# TCRT1.net
KiCad netlist of a schematic drawn in EAGLE
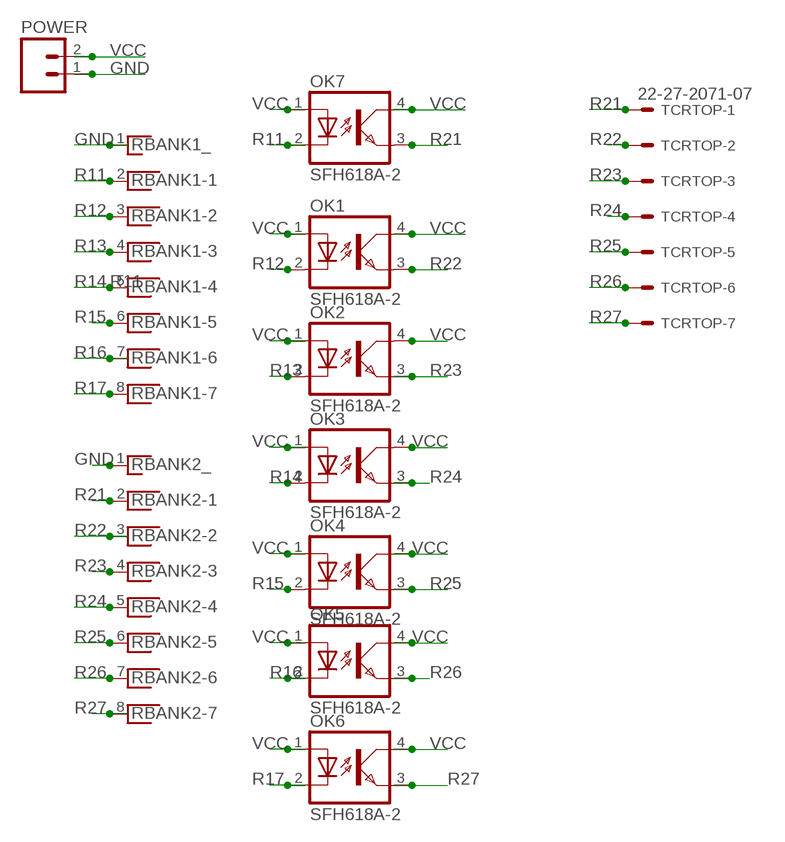
[diagram p0: schematic, sheet 1]

(export (version "E")
  (design (tool "Eeschema 10.0.6"))
  (components
    (comp (ref "OK1")
      (value "SFH618A-2")
      (footprint "eagle-import:DIP4")
      (fields (field (name "MF") "VISHAY/TELEFUNKEN"))
      (libsource (lib "eagle-import") (part "SFH618?A-2"))
    )
    (comp (ref "OK2")
      (value "SFH618A-2")
      (footprint "eagle-import:DIP4")
      (fields (field (name "MF") "VISHAY/TELEFUNKEN"))
      (libsource (lib "eagle-import") (part "SFH618?A-2"))
    )
    (comp (ref "OK3")
      (value "SFH618A-2")
      (footprint "eagle-import:DIP4")
      (fields (field (name "MF") "VISHAY/TELEFUNKEN"))
      (libsource (lib "eagle-import") (part "SFH618?A-2"))
    )
    (comp (ref "OK4")
      (value "SFH618A-2")
      (footprint "eagle-import:DIP4")
      (fields (field (name "MF") "VISHAY/TELEFUNKEN"))
      (libsource (lib "eagle-import") (part "SFH618?A-2"))
    )
    (comp (ref "OK5")
      (value "SFH618A-2")
      (footprint "eagle-import:DIP4")
      (fields (field (name "MF") "VISHAY/TELEFUNKEN"))
      (libsource (lib "eagle-import") (part "SFH618?A-2"))
    )
    (comp (ref "OK6")
      (value "SFH618A-2")
      (footprint "eagle-import:DIP4")
      (fields (field (name "MF") "VISHAY/TELEFUNKEN"))
      (libsource (lib "eagle-import") (part "SFH618?A-2"))
    )
    (comp (ref "OK7")
      (value "SFH618A-2")
      (footprint "eagle-import:DIP4")
      (fields (field (name "MF") "VISHAY/TELEFUNKEN"))
      (libsource (lib "eagle-import") (part "SFH618?A-2"))
    )
    (comp (ref "POWER")
      (value "M025MM")
      (footprint "eagle-import:SCREWTERMINAL-5MM-2")
      (libsource (lib "eagle-import") (part "M025MM"))
    )
    (comp (ref "RBANK1")
      (value "RNX7")
      (footprint "eagle-import:RN-8")
      (libsource (lib "eagle-import") (part "RNX7"))
    )
    (comp (ref "RBANK2")
      (value "RNX7")
      (footprint "eagle-import:RN-8")
      (libsource (lib "eagle-import") (part "RNX7"))
    )
    (comp (ref "TCRTOP")
      (value "22-27-2071-07")
      (footprint "eagle-import:6410-07")
      (libsource (lib "eagle-import") (part "22-?-0727-2071"))
    )
  )
  (nets
    (net (code "1") (name "/GND") (class "Default")
      (node (ref "POWER") (pin "1") (pinfunction "1_1") (pintype "passive"))
      (node (ref "RBANK1") (pin "1") (pinfunction "1_1") (pintype "passive"))
      (node (ref "RBANK2") (pin "1") (pinfunction "1_1") (pintype "passive"))
    )
    (net (code "2") (name "/R11") (class "Default")
      (node (ref "OK7") (pin "2") (pinfunction "C_2") (pintype "passive"))
      (node (ref "RBANK1") (pin "2") (pinfunction "1_2") (pintype "passive"))
    )
    (net (code "3") (name "/R12") (class "Default")
      (node (ref "OK1") (pin "2") (pinfunction "C_2") (pintype "passive"))
      (node (ref "RBANK1") (pin "3") (pinfunction "1_3") (pintype "passive"))
    )
    (net (code "4") (name "/R13") (class "Default")
      (node (ref "OK2") (pin "2") (pinfunction "C_2") (pintype "passive"))
      (node (ref "RBANK1") (pin "4") (pinfunction "1_4") (pintype "passive"))
    )
    (net (code "5") (name "/R14") (class "Default")
      (node (ref "OK3") (pin "2") (pinfunction "C_2") (pintype "passive"))
      (node (ref "RBANK1") (pin "5") (pinfunction "1_5") (pintype "passive"))
    )
    (net (code "6") (name "/R15") (class "Default")
      (node (ref "OK4") (pin "2") (pinfunction "C_2") (pintype "passive"))
      (node (ref "RBANK1") (pin "6") (pinfunction "1_6") (pintype "passive"))
    )
    (net (code "7") (name "/R16") (class "Default")
      (node (ref "OK5") (pin "2") (pinfunction "C_2") (pintype "passive"))
      (node (ref "RBANK1") (pin "7") (pinfunction "1_7") (pintype "passive"))
    )
    (net (code "8") (name "/R17") (class "Default")
      (node (ref "OK6") (pin "2") (pinfunction "C_2") (pintype "passive"))
      (node (ref "RBANK1") (pin "8") (pinfunction "1_8") (pintype "passive"))
    )
    (net (code "9") (name "/R21") (class "Default")
      (node (ref "OK7") (pin "3") (pinfunction "EMIT_3") (pintype "passive"))
      (node (ref "RBANK2") (pin "2") (pinfunction "1_2") (pintype "passive"))
      (node (ref "TCRTOP") (pin "1") (pinfunction "S_1") (pintype "passive"))
    )
    (net (code "10") (name "/R22") (class "Default")
      (node (ref "OK1") (pin "3") (pinfunction "EMIT_3") (pintype "passive"))
      (node (ref "RBANK2") (pin "3") (pinfunction "1_3") (pintype "passive"))
      (node (ref "TCRTOP") (pin "2") (pinfunction "S_2") (pintype "passive"))
    )
    (net (code "11") (name "/R23") (class "Default")
      (node (ref "OK2") (pin "3") (pinfunction "EMIT_3") (pintype "passive"))
      (node (ref "RBANK2") (pin "4") (pinfunction "1_4") (pintype "passive"))
      (node (ref "TCRTOP") (pin "3") (pinfunction "S_3") (pintype "passive"))
    )
    (net (code "12") (name "/R24") (class "Default")
      (node (ref "OK3") (pin "3") (pinfunction "EMIT_3") (pintype "passive"))
      (node (ref "RBANK2") (pin "5") (pinfunction "1_5") (pintype "passive"))
      (node (ref "TCRTOP") (pin "4") (pinfunction "S_4") (pintype "passive"))
    )
    (net (code "13") (name "/R25") (class "Default")
      (node (ref "OK4") (pin "3") (pinfunction "EMIT_3") (pintype "passive"))
      (node (ref "RBANK2") (pin "6") (pinfunction "1_6") (pintype "passive"))
      (node (ref "TCRTOP") (pin "5") (pinfunction "S_5") (pintype "passive"))
    )
    (net (code "14") (name "/R26") (class "Default")
      (node (ref "OK5") (pin "3") (pinfunction "EMIT_3") (pintype "passive"))
      (node (ref "RBANK2") (pin "7") (pinfunction "1_7") (pintype "passive"))
      (node (ref "TCRTOP") (pin "6") (pinfunction "S_6") (pintype "passive"))
    )
    (net (code "15") (name "/R27") (class "Default")
      (node (ref "OK6") (pin "3") (pinfunction "EMIT_3") (pintype "passive"))
      (node (ref "RBANK2") (pin "8") (pinfunction "1_8") (pintype "passive"))
      (node (ref "TCRTOP") (pin "7") (pinfunction "S_7") (pintype "passive"))
    )
    (net (code "16") (name "/VCC") (class "Default")
      (node (ref "OK1") (pin "1") (pinfunction "A_1") (pintype "passive"))
      (node (ref "OK1") (pin "4") (pinfunction "COL_4") (pintype "passive"))
      (node (ref "OK2") (pin "1") (pinfunction "A_1") (pintype "passive"))
      (node (ref "OK2") (pin "4") (pinfunction "COL_4") (pintype "passive"))
      (node (ref "OK3") (pin "1") (pinfunction "A_1") (pintype "passive"))
      (node (ref "OK3") (pin "4") (pinfunction "COL_4") (pintype "passive"))
      (node (ref "OK4") (pin "1") (pinfunction "A_1") (pintype "passive"))
      (node (ref "OK4") (pin "4") (pinfunction "COL_4") (pintype "passive"))
      (node (ref "OK5") (pin "1") (pinfunction "A_1") (pintype "passive"))
      (node (ref "OK5") (pin "4") (pinfunction "COL_4") (pintype "passive"))
      (node (ref "OK6") (pin "1") (pinfunction "A_1") (pintype "passive"))
      (node (ref "OK6") (pin "4") (pinfunction "COL_4") (pintype "passive"))
      (node (ref "OK7") (pin "1") (pinfunction "A_1") (pintype "passive"))
      (node (ref "OK7") (pin "4") (pinfunction "COL_4") (pintype "passive"))
      (node (ref "POWER") (pin "2") (pinfunction "2_2") (pintype "passive"))
    )
  )
)
